# tinyduino-breakout-mk-5_1.net
KiCad netlist of a schematic drawn in EAGLE
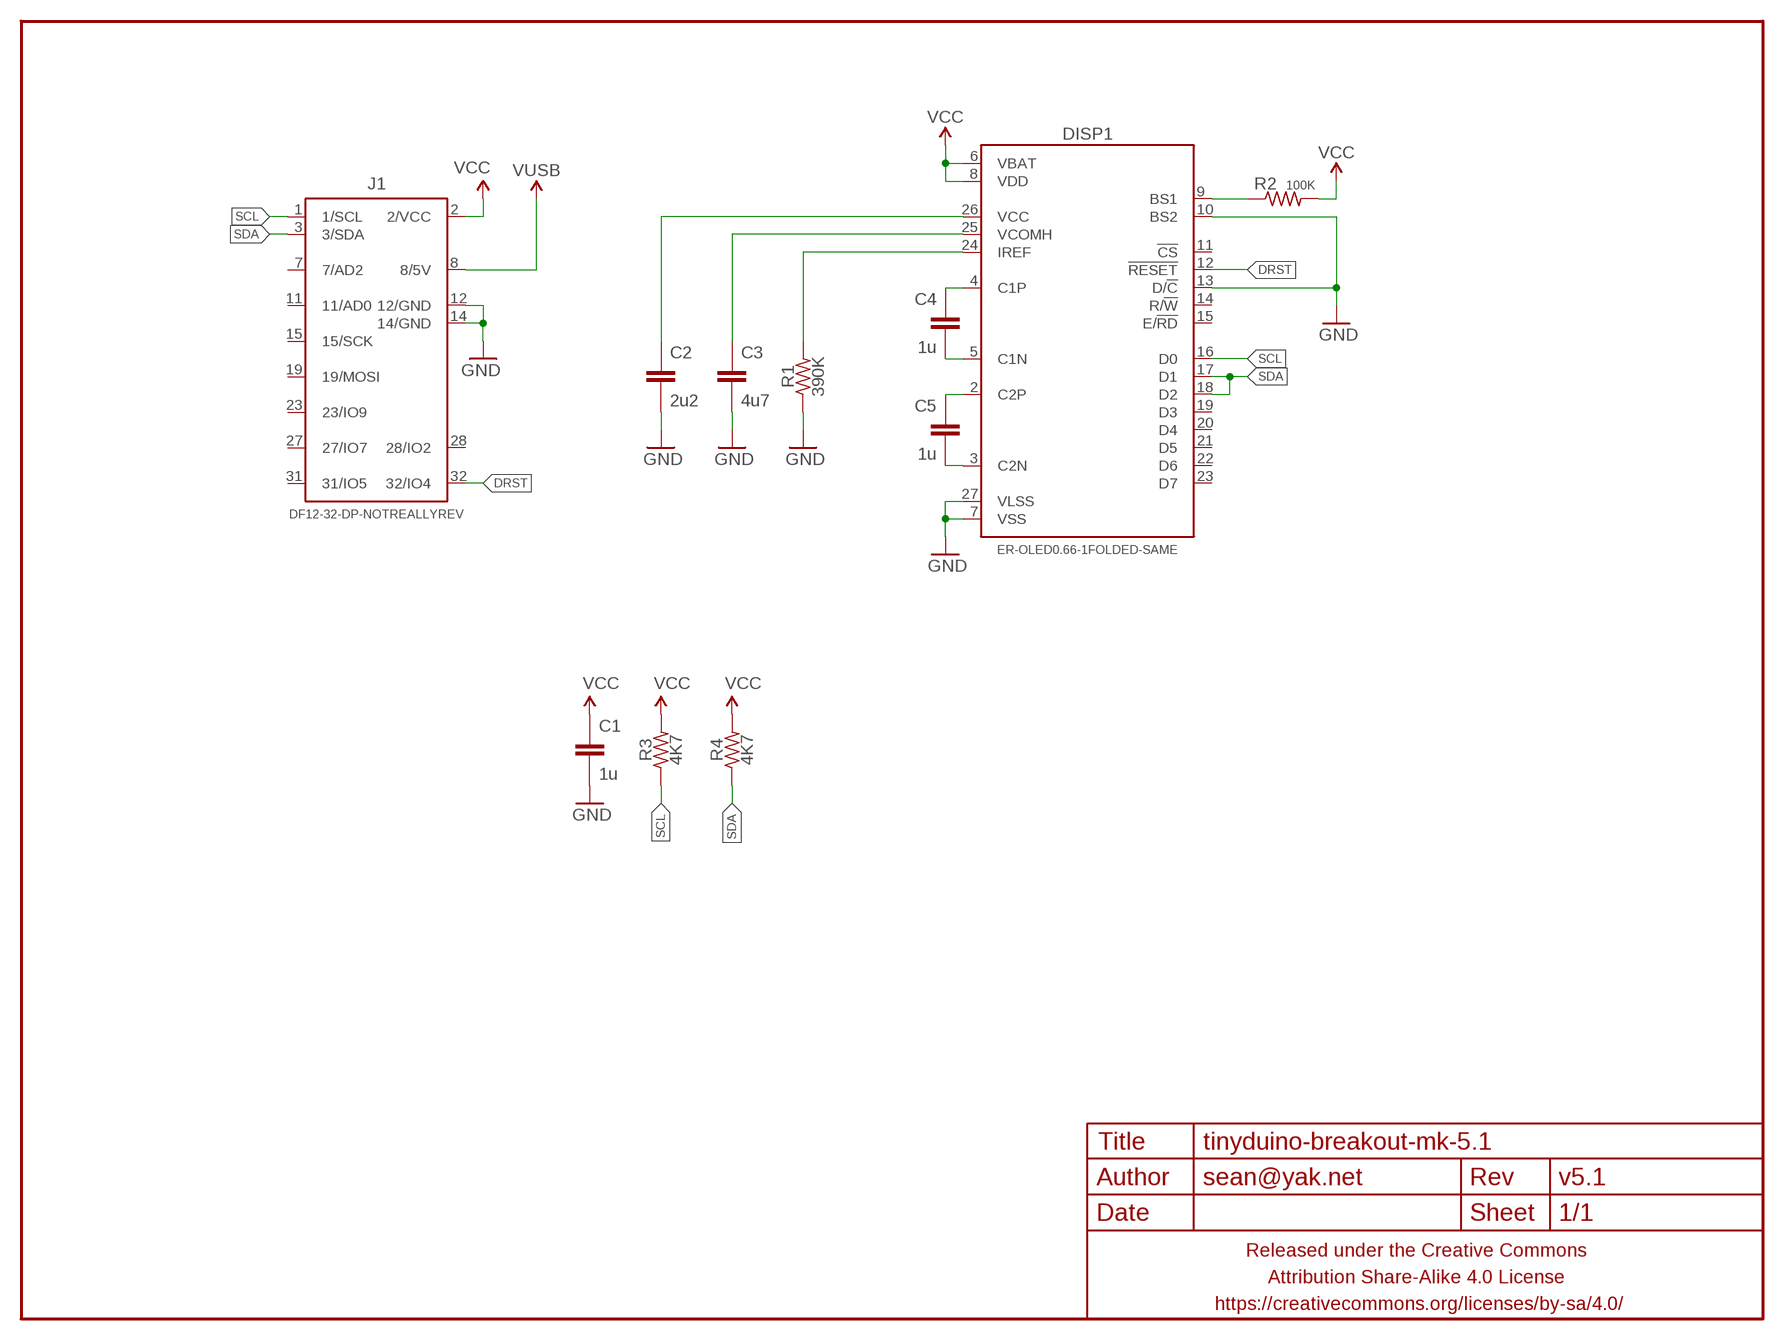
[diagram p0: schematic, sheet 1]

(export (version "E")
  (design (tool "Eeschema 10.0.6"))
  (components
    (comp (ref "C1")
      (value "1u")
      (footprint "eagle-import:C0603")
      (libsource (lib "eagle-import") (part "CAPACITOR-CERAMICC0603"))
    )
    (comp (ref "C2")
      (value "2u2")
      (footprint "eagle-import:C0603")
      (libsource (lib "eagle-import") (part "CAPACITOR-CERAMICC0603"))
    )
    (comp (ref "C3")
      (value "4u7")
      (footprint "eagle-import:C0603")
      (libsource (lib "eagle-import") (part "CAPACITOR-CERAMICC0603"))
    )
    (comp (ref "C4")
      (value "1u")
      (footprint "eagle-import:C0603")
      (libsource (lib "eagle-import") (part "CAPACITOR-CERAMICC0603"))
    )
    (comp (ref "C5")
      (value "1u")
      (footprint "eagle-import:C0603")
      (libsource (lib "eagle-import") (part "CAPACITOR-CERAMICC0603"))
    )
    (comp (ref "DISP1")
      (value "ER-OLED0.66-1FOLDED-SAME")
      (footprint "eagle-import:ER-OLED0.66-1-FOLDED-SAME")
      (libsource (lib "eagle-import") (part "ER-OLED0.66-1FOLDED-SAME"))
    )
    (comp (ref "FRAME1")
      (value "FRAME-LETTERNO_PACKAGE")
      (footprint "eagle-import:DUMMY")
      (fields (field (name "DESIGNER") "sean@yak.net") (field (name "VERSION") "v5.1"))
      (libsource (lib "eagle-import") (part "FRAME-LETTERNO_PACKAGE"))
    )
    (comp (ref "J1")
      (value "DF12-32-DP-NOTREALLYREV")
      (footprint "eagle-import:DF12-32-DP-I2C+EXTRA-REV")
      (libsource (lib "eagle-import") (part "DF12-32-DP-NOTREALLYREV"))
    )
    (comp (ref "R1")
      (value "390K")
      (footprint "eagle-import:R0603")
      (libsource (lib "eagle-import") (part "RESISTORR0603"))
    )
    (comp (ref "R2")
      (value "100K")
      (footprint "eagle-import:R0603")
      (libsource (lib "eagle-import") (part "RESISTORR0603"))
    )
    (comp (ref "R3")
      (value "4K7")
      (footprint "eagle-import:R0603")
      (libsource (lib "eagle-import") (part "RESISTORR0603"))
    )
    (comp (ref "R4")
      (value "4K7")
      (footprint "eagle-import:R0603")
      (libsource (lib "eagle-import") (part "RESISTORR0603"))
    )
  )
  (nets
    (net (code "1") (name "DRST") (class "Default")
      (node (ref "DISP1") (pin "12") (pinfunction "~{RESET}_12") (pintype "bidirectional"))
      (node (ref "J1") (pin "32") (pinfunction "32/IO4_32") (pintype "bidirectional"))
    )
    (net (code "2") (name "GND") (class "Default")
      (node (ref "C1") (pin "2") (pinfunction "2_2") (pintype "passive"))
      (node (ref "C2") (pin "2") (pinfunction "2_2") (pintype "passive"))
      (node (ref "C3") (pin "2") (pinfunction "2_2") (pintype "passive"))
      (node (ref "DISP1") (pin "10") (pinfunction "BS2_10") (pintype "bidirectional"))
      (node (ref "DISP1") (pin "13") (pinfunction "D/~{C}_13") (pintype "bidirectional"))
      (node (ref "DISP1") (pin "27") (pinfunction "VLSS_27") (pintype "bidirectional"))
      (node (ref "DISP1") (pin "7") (pinfunction "VSS_7") (pintype "bidirectional"))
      (node (ref "J1") (pin "12") (pinfunction "12/GND_12") (pintype "bidirectional"))
      (node (ref "J1") (pin "14") (pinfunction "14/GND_14") (pintype "bidirectional"))
      (node (ref "R1") (pin "1") (pinfunction "1_1") (pintype "passive"))
    )
    (net (code "3") (name "Net-(DISP1-BS1)") (class "Default")
      (node (ref "DISP1") (pin "9") (pinfunction "BS1_9") (pintype "bidirectional"))
      (node (ref "R2") (pin "1") (pinfunction "1_1") (pintype "passive"))
    )
    (net (code "4") (name "Net-(DISP1-C1N)") (class "Default")
      (node (ref "C4") (pin "2") (pinfunction "2_2") (pintype "passive"))
      (node (ref "DISP1") (pin "5") (pinfunction "C1N_5") (pintype "bidirectional"))
    )
    (net (code "5") (name "Net-(DISP1-C1P)") (class "Default")
      (node (ref "C4") (pin "1") (pinfunction "1_1") (pintype "passive"))
      (node (ref "DISP1") (pin "4") (pinfunction "C1P_4") (pintype "bidirectional"))
    )
    (net (code "6") (name "Net-(DISP1-C2N)") (class "Default")
      (node (ref "C5") (pin "2") (pinfunction "2_2") (pintype "passive"))
      (node (ref "DISP1") (pin "3") (pinfunction "C2N_3") (pintype "bidirectional"))
    )
    (net (code "7") (name "Net-(DISP1-C2P)") (class "Default")
      (node (ref "C5") (pin "1") (pinfunction "1_1") (pintype "passive"))
      (node (ref "DISP1") (pin "2") (pinfunction "C2P_2") (pintype "bidirectional"))
    )
    (net (code "8") (name "Net-(DISP1-IREF)") (class "Default")
      (node (ref "DISP1") (pin "24") (pinfunction "IREF_24") (pintype "bidirectional"))
      (node (ref "R1") (pin "2") (pinfunction "2_2") (pintype "passive"))
    )
    (net (code "9") (name "Net-(DISP1-VCC)") (class "Default")
      (node (ref "C2") (pin "1") (pinfunction "1_1") (pintype "passive"))
      (node (ref "DISP1") (pin "26") (pinfunction "VCC_26") (pintype "bidirectional"))
    )
    (net (code "10") (name "Net-(DISP1-VCOMH)") (class "Default")
      (node (ref "C3") (pin "1") (pinfunction "1_1") (pintype "passive"))
      (node (ref "DISP1") (pin "25") (pinfunction "VCOMH_25") (pintype "bidirectional"))
    )
    (net (code "11") (name "SCL") (class "Default")
      (node (ref "DISP1") (pin "16") (pinfunction "D0_16") (pintype "bidirectional"))
      (node (ref "J1") (pin "1") (pinfunction "1/SCL_1") (pintype "bidirectional"))
      (node (ref "R3") (pin "1") (pinfunction "1_1") (pintype "passive"))
    )
    (net (code "12") (name "SDA") (class "Default")
      (node (ref "DISP1") (pin "17") (pinfunction "D1_17") (pintype "bidirectional"))
      (node (ref "DISP1") (pin "18") (pinfunction "D2_18") (pintype "bidirectional"))
      (node (ref "J1") (pin "3") (pinfunction "3/SDA_3") (pintype "bidirectional"))
      (node (ref "R4") (pin "1") (pinfunction "1_1") (pintype "passive"))
    )
    (net (code "13") (name "VCC") (class "Default")
      (node (ref "C1") (pin "1") (pinfunction "1_1") (pintype "passive"))
      (node (ref "DISP1") (pin "6") (pinfunction "VBAT_6") (pintype "bidirectional"))
      (node (ref "DISP1") (pin "8") (pinfunction "VDD_8") (pintype "bidirectional"))
      (node (ref "J1") (pin "2") (pinfunction "2/VCC_2") (pintype "bidirectional"))
      (node (ref "R2") (pin "2") (pinfunction "2_2") (pintype "passive"))
      (node (ref "R3") (pin "2") (pinfunction "2_2") (pintype "passive"))
      (node (ref "R4") (pin "2") (pinfunction "2_2") (pintype "passive"))
    )
    (net (code "14") (name "VUSB") (class "Default")
      (node (ref "J1") (pin "8") (pinfunction "8/5V_8") (pintype "bidirectional"))
    )
    (net (code "15") (name "unconnected-(DISP1-D3-Pad19)") (class "Default")
      (node (ref "DISP1") (pin "19") (pinfunction "D3_19") (pintype "bidirectional"))
    )
    (net (code "16") (name "unconnected-(DISP1-D4-Pad20)") (class "Default")
      (node (ref "DISP1") (pin "20") (pinfunction "D4_20") (pintype "bidirectional"))
    )
    (net (code "17") (name "unconnected-(DISP1-D5-Pad21)") (class "Default")
      (node (ref "DISP1") (pin "21") (pinfunction "D5_21") (pintype "bidirectional"))
    )
    (net (code "18") (name "unconnected-(DISP1-D6-Pad22)") (class "Default")
      (node (ref "DISP1") (pin "22") (pinfunction "D6_22") (pintype "bidirectional"))
    )
    (net (code "19") (name "unconnected-(DISP1-D7-Pad23)") (class "Default")
      (node (ref "DISP1") (pin "23") (pinfunction "D7_23") (pintype "bidirectional"))
    )
    (net (code "20") (name "unconnected-(DISP1-E{slash}~{RD}-Pad15)") (class "Default")
      (node (ref "DISP1") (pin "15") (pinfunction "E/~{RD}_15") (pintype "bidirectional"))
    )
    (net (code "21") (name "unconnected-(DISP1-R{slash}~{W}-Pad14)") (class "Default")
      (node (ref "DISP1") (pin "14") (pinfunction "R/~{W}_14") (pintype "bidirectional"))
    )
    (net (code "22") (name "unconnected-(DISP1-~{CS}-Pad11)") (class "Default")
      (node (ref "DISP1") (pin "11") (pinfunction "~{CS}_11") (pintype "bidirectional"))
    )
    (net (code "23") (name "unconnected-(J1-7{slash}AD2-Pad7)") (class "Default")
      (node (ref "J1") (pin "7") (pinfunction "7/AD2_7") (pintype "bidirectional"))
    )
    (net (code "24") (name "unconnected-(J1-11{slash}AD0-Pad11)") (class "Default")
      (node (ref "J1") (pin "11") (pinfunction "11/AD0_11") (pintype "bidirectional"))
    )
    (net (code "25") (name "unconnected-(J1-15{slash}SCK-Pad15)") (class "Default")
      (node (ref "J1") (pin "15") (pinfunction "15/SCK_15") (pintype "bidirectional"))
    )
    (net (code "26") (name "unconnected-(J1-19{slash}MOSI-Pad19)") (class "Default")
      (node (ref "J1") (pin "19") (pinfunction "19/MOSI_19") (pintype "bidirectional"))
    )
    (net (code "27") (name "unconnected-(J1-23{slash}IO9-Pad23)") (class "Default")
      (node (ref "J1") (pin "23") (pinfunction "23/IO9_23") (pintype "bidirectional"))
    )
    (net (code "28") (name "unconnected-(J1-27{slash}IO7-Pad27)") (class "Default")
      (node (ref "J1") (pin "27") (pinfunction "27/IO7_27") (pintype "bidirectional"))
    )
    (net (code "29") (name "unconnected-(J1-28{slash}IO2-Pad28)") (class "Default")
      (node (ref "J1") (pin "28") (pinfunction "28/IO2_28") (pintype "bidirectional"))
    )
    (net (code "30") (name "unconnected-(J1-31{slash}IO5-Pad31)") (class "Default")
      (node (ref "J1") (pin "31") (pinfunction "31/IO5_31") (pintype "bidirectional"))
    )
  )
)
